# rapoukChargingPCBv0.net
KiCad netlist of a schematic drawn in EasyEDA
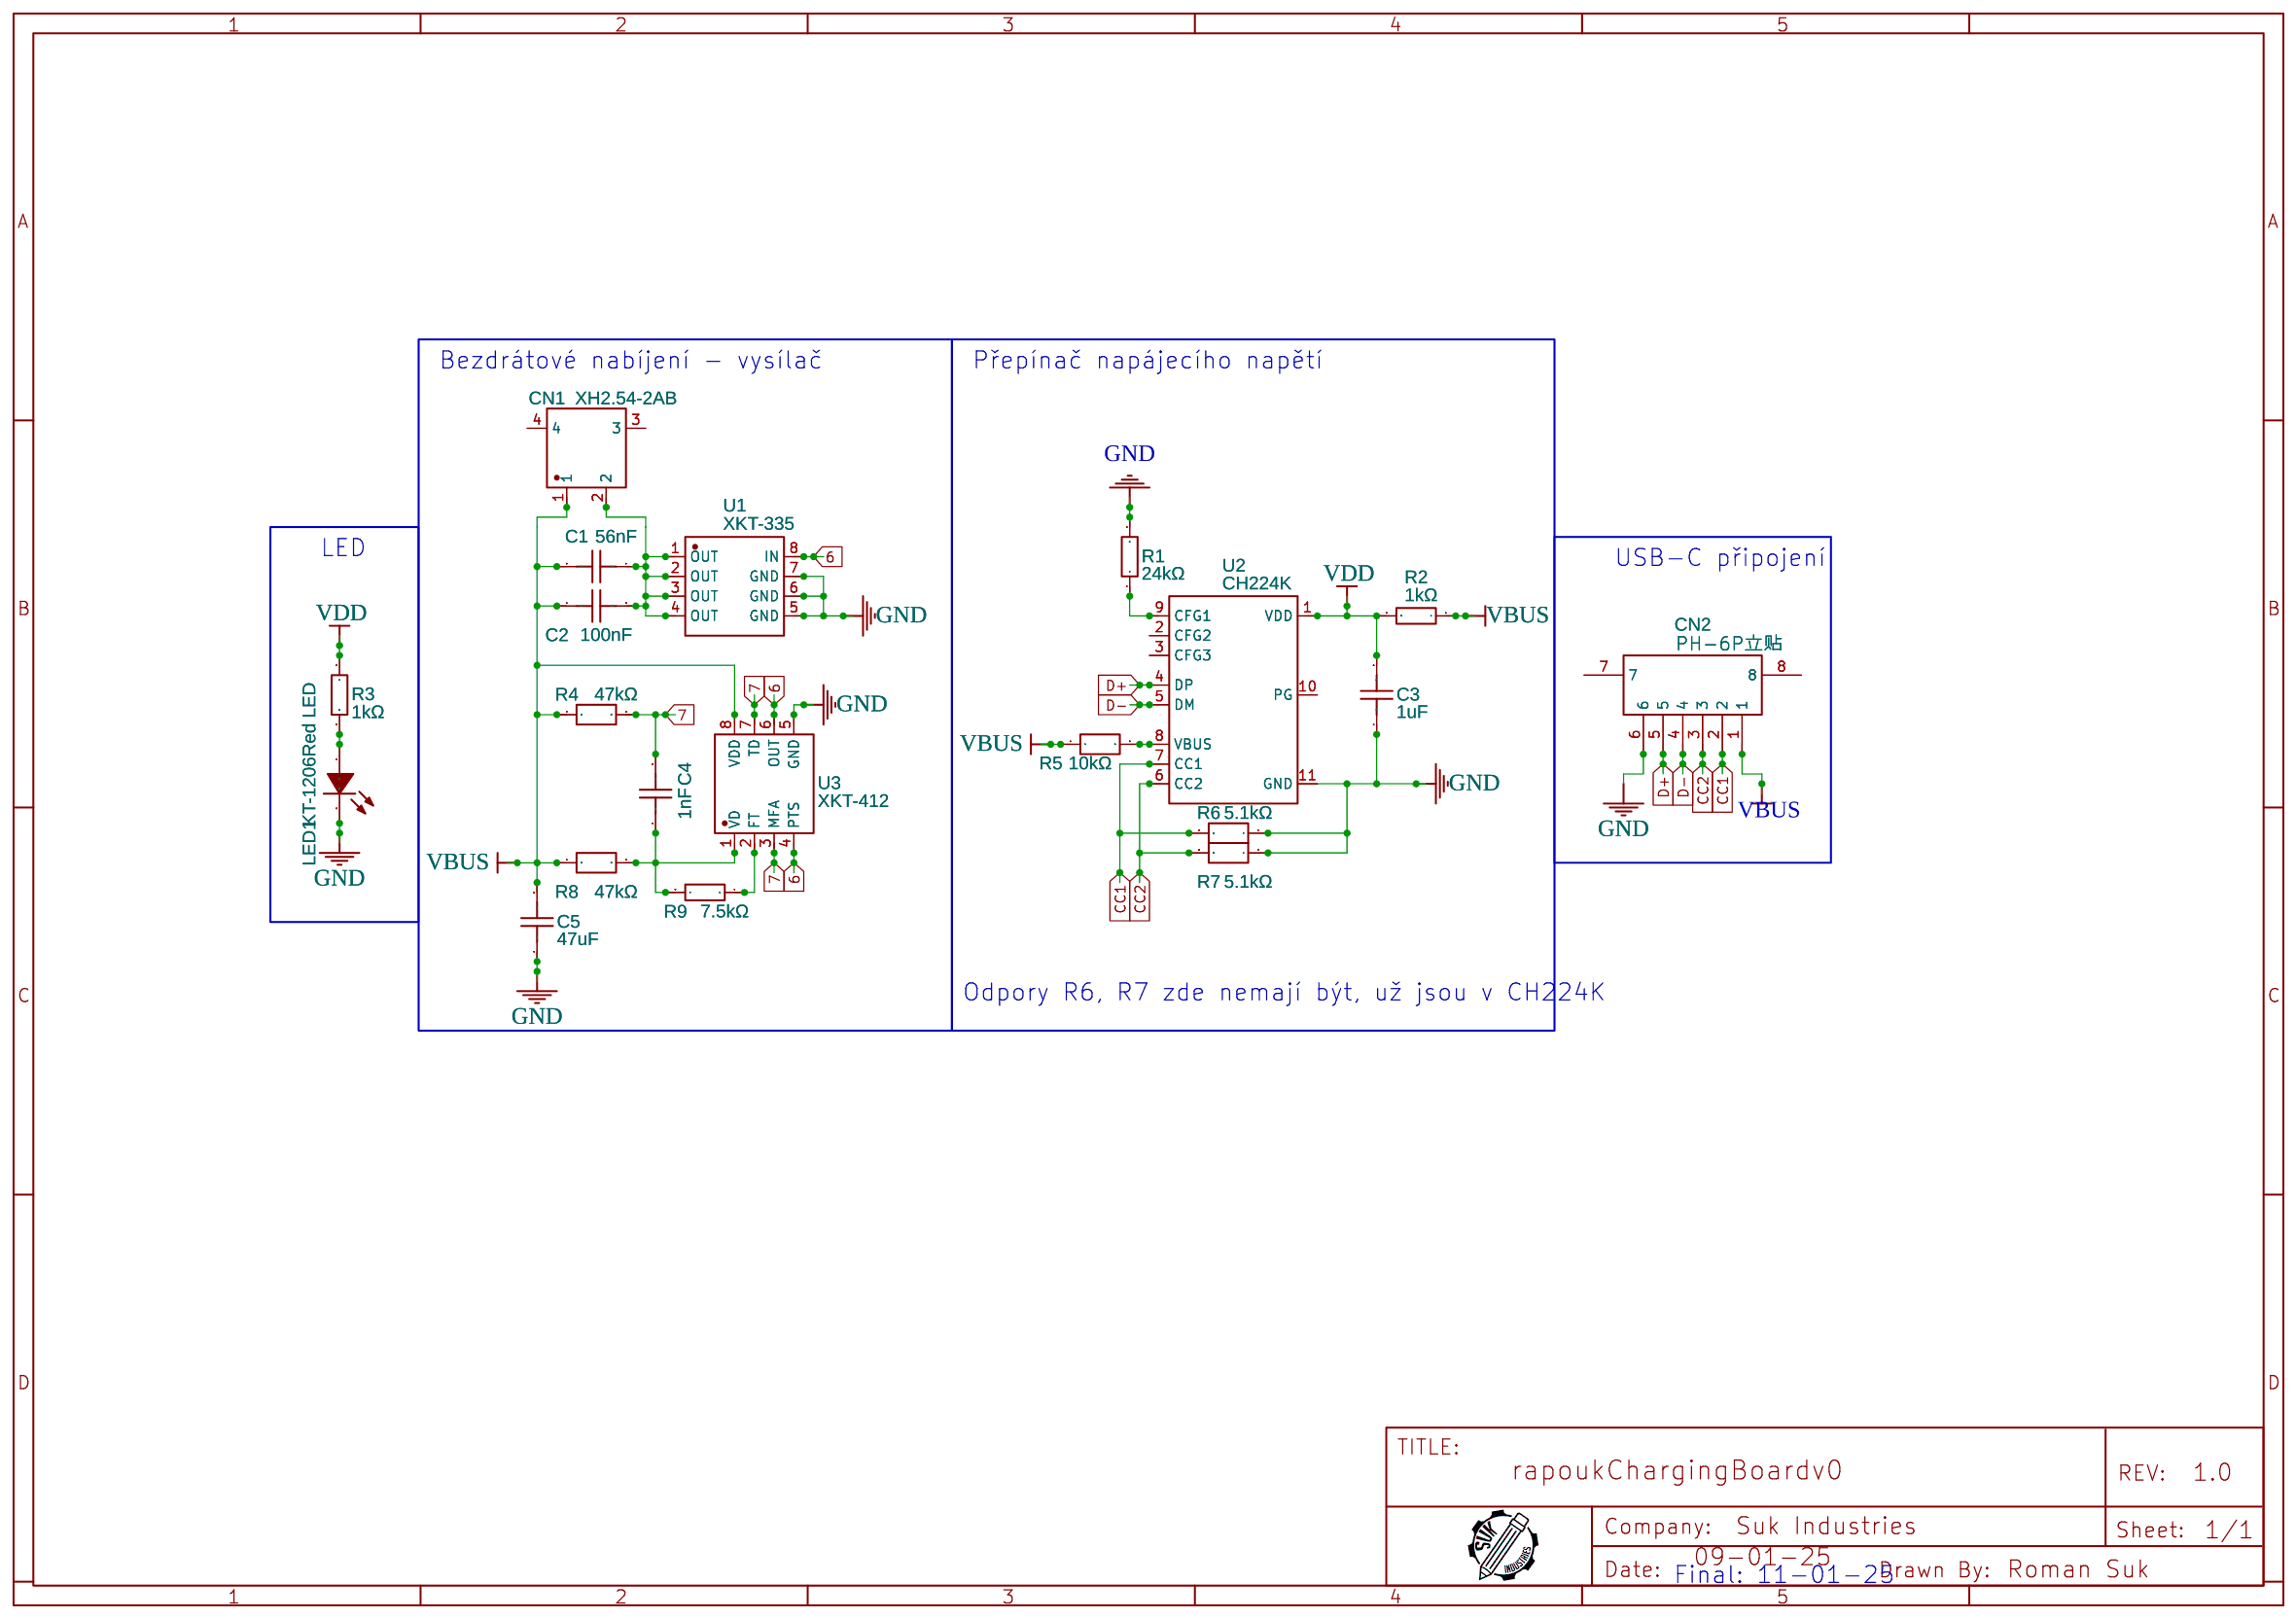
[diagram p0: schematic sheet]

(export (version "E")
  (design (tool "Eeschema 10.0.6"))
  (components
    (comp (ref "C1")
      (value "56nF")
      (fields
        (field (name "Manufacturer Part") "TCC1206X7R563K500DT")
        (field (name "Manufacturer") "CCTC(三环)")
      )
      (libsource (lib "") (part "TCC1206X7R563K500DT"))
    )
    (comp (ref "C2")
      (value "100nF")
      (fields
        (field (name "Manufacturer Part") "CL31B104KBCNNNL")
        (field (name "Manufacturer") "SAMSUNG(三星)")
      )
      (libsource (lib "") (part "CL31B104KBCNNNL"))
    )
    (comp (ref "C3")
      (value "1uF")
      (fields
        (field (name "Manufacturer Part") "C1206X105K5RAC7800")
        (field (name "Manufacturer") "KEMET(基美)")
      )
      (libsource (lib "") (part "C1206X105K5RAC7800"))
    )
    (comp (ref "C4")
      (value "1nF")
      (fields
        (field (name "Manufacturer Part") "500R18N102JV4T")
        (field (name "Manufacturer") "JOHANSON(约翰逊)")
      )
      (libsource (lib "") (part "500R18N102JV4T"))
    )
    (comp (ref "C5")
      (value "47uF")
      (fields
        (field (name "Manufacturer Part") "LMK316ABJ476ML-T")
        (field (name "Manufacturer") "TAIYO YUDEN(太诱)")
      )
      (libsource (lib "") (part "LMK316ABJ476ML-T"))
    )
    (comp (ref "CN1")
      (value "XH2.54-2AB")
      (fields (field (name "Manufacturer Part") "XH-2P立贴") (field (name "Manufacturer") "BOOMELE(博穆精密)"))
      (libsource (lib "") (part "XH2.54-2AB"))
    )
    (comp (ref "CN2")
      (value "PH-6P立贴")
      (fields (field (name "Manufacturer") "BOOMELE(博穆精密)"))
      (libsource (lib "") (part "PH-6P立贴"))
    )
    (comp (ref "LED1")
      (value "KT-1206Red LED")
      (fields (field (name "Manufacturer Part") "KT-1206R") (field (name "Manufacturer") "KENTO"))
      (libsource (lib "") (part "KT-1206Red LED"))
    )
    (comp (ref "R1")
      (value "24kΩ")
      (fields (field (name "Manufacturer Part") "AECR1206F24K0K9") (field (name "Manufacturer") "RESI(开步睿思)"))
      (libsource (lib "") (part "AECR1206F24K0K9"))
    )
    (comp (ref "R2")
      (value "1kΩ")
      (fields (field (name "Manufacturer Part") "CR1206-FX-1001ELF") (field (name "Manufacturer") "BOURNS"))
      (libsource (lib "") (part "CR1206-FX-1001ELF_1"))
    )
    (comp (ref "R3")
      (value "1kΩ")
      (fields (field (name "Manufacturer Part") "CR1206-FX-1001ELF") (field (name "Manufacturer") "BOURNS"))
      (libsource (lib "") (part "CR1206-FX-1001ELF"))
    )
    (comp (ref "R4")
      (value "47kΩ")
      (fields
        (field (name "Manufacturer Part") "CR1206J47K0P05Z")
        (field (name "Manufacturer") "EVER OHMS(天二科技)")
      )
      (libsource (lib "") (part "CR1206J47K0P05Z"))
    )
    (comp (ref "R5")
      (value "10kΩ")
      (fields (field (name "Manufacturer Part") "PTFR1206B10K0N9") (field (name "Manufacturer") "RESI(开步睿思)"))
      (libsource (lib "") (part "PTFR1206B10K0N9"))
    )
    (comp (ref "R6")
      (value "5.1kΩ")
      (fields
        (field (name "Manufacturer Part") "HoARG0603-1/10W-5.1KR-0.1%-TCR25")
        (field (name "Manufacturer") "Milliohm(毫欧)")
      )
      (libsource (lib "") (part "HOARG0603-1/10W-5.1KR-0.1%-TCR25"))
    )
    (comp (ref "R7")
      (value "5.1kΩ")
      (fields
        (field (name "Manufacturer Part") "HoARG0603-1/10W-5.1KR-0.1%-TCR25")
        (field (name "Manufacturer") "Milliohm(毫欧)")
      )
      (libsource (lib "") (part "HOARG0603-1/10W-5.1KR-0.1%-TCR25"))
    )
    (comp (ref "R8")
      (value "47kΩ")
      (fields
        (field (name "Manufacturer Part") "CR1206J47K0P05Z")
        (field (name "Manufacturer") "EVER OHMS(天二科技)")
      )
      (libsource (lib "") (part "CR1206J47K0P05Z"))
    )
    (comp (ref "R9")
      (value "7.5kΩ")
      (fields (field (name "Manufacturer Part") "CR1206J40752G") (field (name "Manufacturer") "LIZ(丽智电子)"))
      (libsource (lib "") (part "CR1206J40752G"))
    )
    (comp (ref "U1") (value "XKT-335") (libsource (lib "") (part "XKT-335")))
    (comp (ref "U2")
      (value "CH224K")
      (fields (field (name "Manufacturer") "WCH(南京沁恒)"))
      (libsource (lib "") (part "CH224K"))
    )
    (comp (ref "U3") (value "XKT-412") (libsource (lib "") (part "XKT-412")))
  )
  (nets
    (net (code "1") (name "6") (class "Default")
      (node (ref "U1") (pin "8") (pinfunction "IN_8") (pintype "unspecified"))
      (node (ref "U3") (pin "4") (pinfunction "PTS_4") (pintype "unspecified"))
      (node (ref "U3") (pin "6") (pinfunction "OUT_6") (pintype "unspecified"))
    )
    (net (code "2") (name "7") (class "Default")
      (node (ref "C4") (pin "2") (pinfunction "2_2") (pintype "unspecified"))
      (node (ref "R4") (pin "2") (pinfunction "2_2") (pintype "unspecified"))
      (node (ref "U3") (pin "3") (pinfunction "MFA_3") (pintype "unspecified"))
      (node (ref "U3") (pin "7") (pinfunction "TD_7") (pintype "unspecified"))
    )
    (net (code "3") (name "CC1") (class "Default")
      (node (ref "CN2") (pin "2") (pinfunction "2_2") (pintype "unspecified"))
      (node (ref "R6") (pin "2") (pinfunction "2_2") (pintype "unspecified"))
      (node (ref "U2") (pin "7") (pinfunction "CC1_7") (pintype "unspecified"))
    )
    (net (code "4") (name "CC2") (class "Default")
      (node (ref "CN2") (pin "3") (pinfunction "3_3") (pintype "unspecified"))
      (node (ref "R7") (pin "2") (pinfunction "2_2") (pintype "unspecified"))
      (node (ref "U2") (pin "6") (pinfunction "CC2_6") (pintype "unspecified"))
    )
    (net (code "5") (name "D+") (class "Default")
      (node (ref "CN2") (pin "5") (pinfunction "5_5") (pintype "unspecified"))
      (node (ref "U2") (pin "4") (pinfunction "DP_4") (pintype "unspecified"))
    )
    (net (code "6") (name "D-") (class "Default")
      (node (ref "CN2") (pin "4") (pinfunction "4_4") (pintype "unspecified"))
      (node (ref "U2") (pin "5") (pinfunction "DM_5") (pintype "unspecified"))
    )
    (net (code "7") (name "GND") (class "Default")
      (node (ref "C3") (pin "1") (pinfunction "1_1") (pintype "unspecified"))
      (node (ref "C5") (pin "1") (pinfunction "1_1") (pintype "unspecified"))
      (node (ref "CN2") (pin "6") (pinfunction "6_6") (pintype "unspecified"))
      (node (ref "LED1") (pin "2") (pinfunction "K_2") (pintype "unspecified"))
      (node (ref "R1") (pin "2") (pinfunction "2_2") (pintype "unspecified"))
      (node (ref "R6") (pin "1") (pinfunction "1_1") (pintype "unspecified"))
      (node (ref "R7") (pin "1") (pinfunction "1_1") (pintype "unspecified"))
      (node (ref "U1") (pin "5") (pinfunction "GND_5") (pintype "unspecified"))
      (node (ref "U1") (pin "6") (pinfunction "GND_6") (pintype "unspecified"))
      (node (ref "U1") (pin "7") (pinfunction "GND_7") (pintype "unspecified"))
      (node (ref "U2") (pin "11") (pinfunction "GND_11") (pintype "unspecified"))
      (node (ref "U3") (pin "5") (pinfunction "GND_5") (pintype "unspecified"))
    )
    (net (code "8") (name "Net-(C1-Pad1)") (class "Default")
      (node (ref "C1") (pin "1") (pinfunction "1_1") (pintype "unspecified"))
      (node (ref "C2") (pin "2") (pinfunction "2_2") (pintype "unspecified"))
      (node (ref "CN1") (pin "2") (pinfunction "2_2") (pintype "unspecified"))
      (node (ref "U1") (pin "1") (pinfunction "OUT_1") (pintype "unspecified"))
      (node (ref "U1") (pin "2") (pinfunction "OUT_2") (pintype "unspecified"))
      (node (ref "U1") (pin "3") (pinfunction "OUT_3") (pintype "unspecified"))
      (node (ref "U1") (pin "4") (pinfunction "OUT_4") (pintype "unspecified"))
    )
    (net (code "9") (name "Net-(LED1-A)") (class "Default")
      (node (ref "LED1") (pin "1") (pinfunction "A_1") (pintype "unspecified"))
      (node (ref "R3") (pin "2") (pinfunction "2_2") (pintype "unspecified"))
    )
    (net (code "10") (name "Net-(U2-CFG1)") (class "Default")
      (node (ref "R1") (pin "1") (pinfunction "1_1") (pintype "unspecified"))
      (node (ref "U2") (pin "9") (pinfunction "CFG1_9") (pintype "unspecified"))
    )
    (net (code "11") (name "Net-(U2-VBUS)") (class "Default")
      (node (ref "R5") (pin "2") (pinfunction "2_2") (pintype "unspecified"))
      (node (ref "U2") (pin "8") (pinfunction "VBUS_8") (pintype "unspecified"))
    )
    (net (code "12") (name "Net-(U3-FT)") (class "Default")
      (node (ref "R9") (pin "1") (pinfunction "1_1") (pintype "input"))
      (node (ref "U3") (pin "2") (pinfunction "FT_2") (pintype "unspecified"))
    )
    (net (code "13") (name "Net-(U3-VD)") (class "Default")
      (node (ref "C4") (pin "1") (pinfunction "1_1") (pintype "unspecified"))
      (node (ref "R8") (pin "2") (pinfunction "2_2") (pintype "unspecified"))
      (node (ref "R9") (pin "2") (pinfunction "2_2") (pintype "input"))
      (node (ref "U3") (pin "1") (pinfunction "VD_1") (pintype "unspecified"))
    )
    (net (code "14") (name "VBUS") (class "Default")
      (node (ref "C1") (pin "2") (pinfunction "2_2") (pintype "unspecified"))
      (node (ref "C2") (pin "1") (pinfunction "1_1") (pintype "unspecified"))
      (node (ref "C5") (pin "2") (pinfunction "2_2") (pintype "unspecified"))
      (node (ref "CN1") (pin "1") (pinfunction "1_1") (pintype "unspecified"))
      (node (ref "CN2") (pin "1") (pinfunction "1_1") (pintype "unspecified"))
      (node (ref "R2") (pin "1") (pinfunction "1_1") (pintype "unspecified"))
      (node (ref "R4") (pin "1") (pinfunction "1_1") (pintype "unspecified"))
      (node (ref "R5") (pin "1") (pinfunction "1_1") (pintype "unspecified"))
      (node (ref "R8") (pin "1") (pinfunction "1_1") (pintype "unspecified"))
      (node (ref "U3") (pin "8") (pinfunction "VDD_8") (pintype "unspecified"))
    )
    (net (code "15") (name "VDD") (class "Default")
      (node (ref "C3") (pin "2") (pinfunction "2_2") (pintype "unspecified"))
      (node (ref "R2") (pin "2") (pinfunction "2_2") (pintype "unspecified"))
      (node (ref "R3") (pin "1") (pinfunction "1_1") (pintype "unspecified"))
      (node (ref "U2") (pin "1") (pinfunction "VDD_1") (pintype "unspecified"))
    )
    (net (code "16") (name "unconnected-(CN1-Pad3)") (class "Default")
      (node (ref "CN1") (pin "3") (pinfunction "3_3") (pintype "unspecified"))
    )
    (net (code "17") (name "unconnected-(CN1-Pad4)") (class "Default")
      (node (ref "CN1") (pin "4") (pinfunction "4_4") (pintype "unspecified"))
    )
    (net (code "18") (name "unconnected-(CN2-Pad7)") (class "Default")
      (node (ref "CN2") (pin "7") (pinfunction "7_7") (pintype "unspecified"))
    )
    (net (code "19") (name "unconnected-(CN2-Pad8)") (class "Default")
      (node (ref "CN2") (pin "8") (pinfunction "8_8") (pintype "unspecified"))
    )
    (net (code "20") (name "unconnected-(U2-CFG2-Pad2)") (class "Default")
      (node (ref "U2") (pin "2") (pinfunction "CFG2_2") (pintype "unspecified"))
    )
    (net (code "21") (name "unconnected-(U2-CFG3-Pad3)") (class "Default")
      (node (ref "U2") (pin "3") (pinfunction "CFG3_3") (pintype "unspecified"))
    )
    (net (code "22") (name "unconnected-(U2-PG-Pad10)") (class "Default")
      (node (ref "U2") (pin "10") (pinfunction "PG_10") (pintype "unspecified"))
    )
  )
)
